# potentiometer.net
KiCad netlist of a schematic drawn in EAGLE
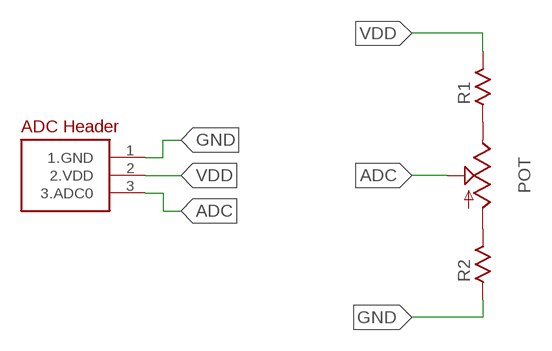
[diagram p0: schematic, sheet 1]

(export (version "E")
  (design (tool "Eeschema 10.0.6"))
  (components
    (comp (ref "POT")
      (value "TRIM3386")
      (footprint "eagle-import:TRIM-3386")
      (libsource (lib "eagle-import") (part "TRIM3386"))
    )
    (comp (ref "R1")
      (value "R0805")
      (footprint "eagle-import:R0805")
      (libsource (lib "eagle-import") (part "R0805"))
    )
    (comp (ref "R2")
      (value "R0805")
      (footprint "eagle-import:R0805")
      (libsource (lib "eagle-import") (part "R0805"))
    )
    (comp (ref "U$1")
      (value "VIVA-HEADER-ADC-1")
      (footprint "eagle-import:VIVA-HEADER-ADC-RA-2")
      (libsource (lib "eagle-import") (part "VIVA-HEADER-ADC-1"))
    )
  )
  (nets
    (net (code "1") (name "ADC") (class "Default")
      (node (ref "POT") (pin "2") (pinfunction "S_2") (pintype "passive"))
      (node (ref "U$1") (pin "3") (pinfunction "3.ADC0_3") (pintype "bidirectional"))
    )
    (net (code "2") (name "GND") (class "Default")
      (node (ref "R2") (pin "1") (pinfunction "P$1_1") (pintype "bidirectional"))
      (node (ref "U$1") (pin "1") (pinfunction "1.GND_1") (pintype "bidirectional"))
    )
    (net (code "3") (name "Net-(POT-A)") (class "Default")
      (node (ref "POT") (pin "3") (pinfunction "A_3") (pintype "passive"))
      (node (ref "R2") (pin "2") (pinfunction "P$2_2") (pintype "bidirectional"))
    )
    (net (code "4") (name "Net-(POT-E)") (class "Default")
      (node (ref "POT") (pin "1") (pinfunction "E_1") (pintype "passive"))
      (node (ref "R1") (pin "1") (pinfunction "P$1_1") (pintype "bidirectional"))
    )
    (net (code "5") (name "VDD") (class "Default")
      (node (ref "R1") (pin "2") (pinfunction "P$2_2") (pintype "bidirectional"))
      (node (ref "U$1") (pin "2") (pinfunction "2.VDD_2") (pintype "bidirectional"))
    )
  )
)
